# FPGA_0.net
KiCad netlist of a schematic drawn in Altium Designer
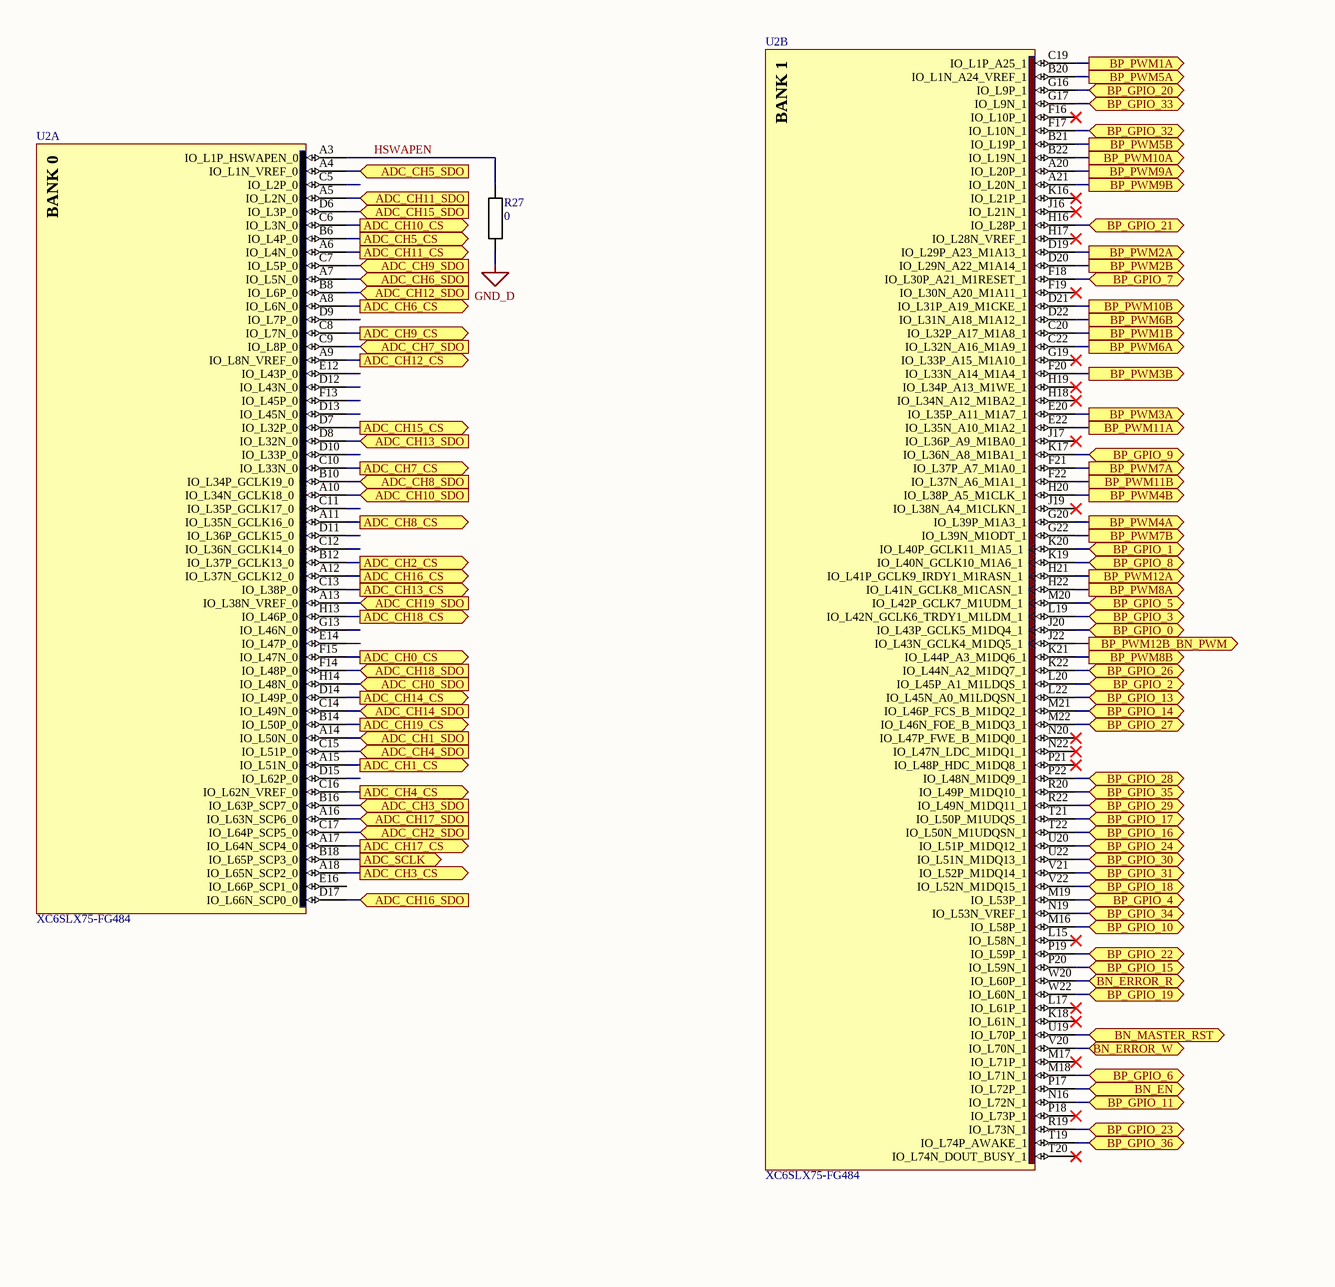
[diagram p0: FPGA_0.SchDoc, left]
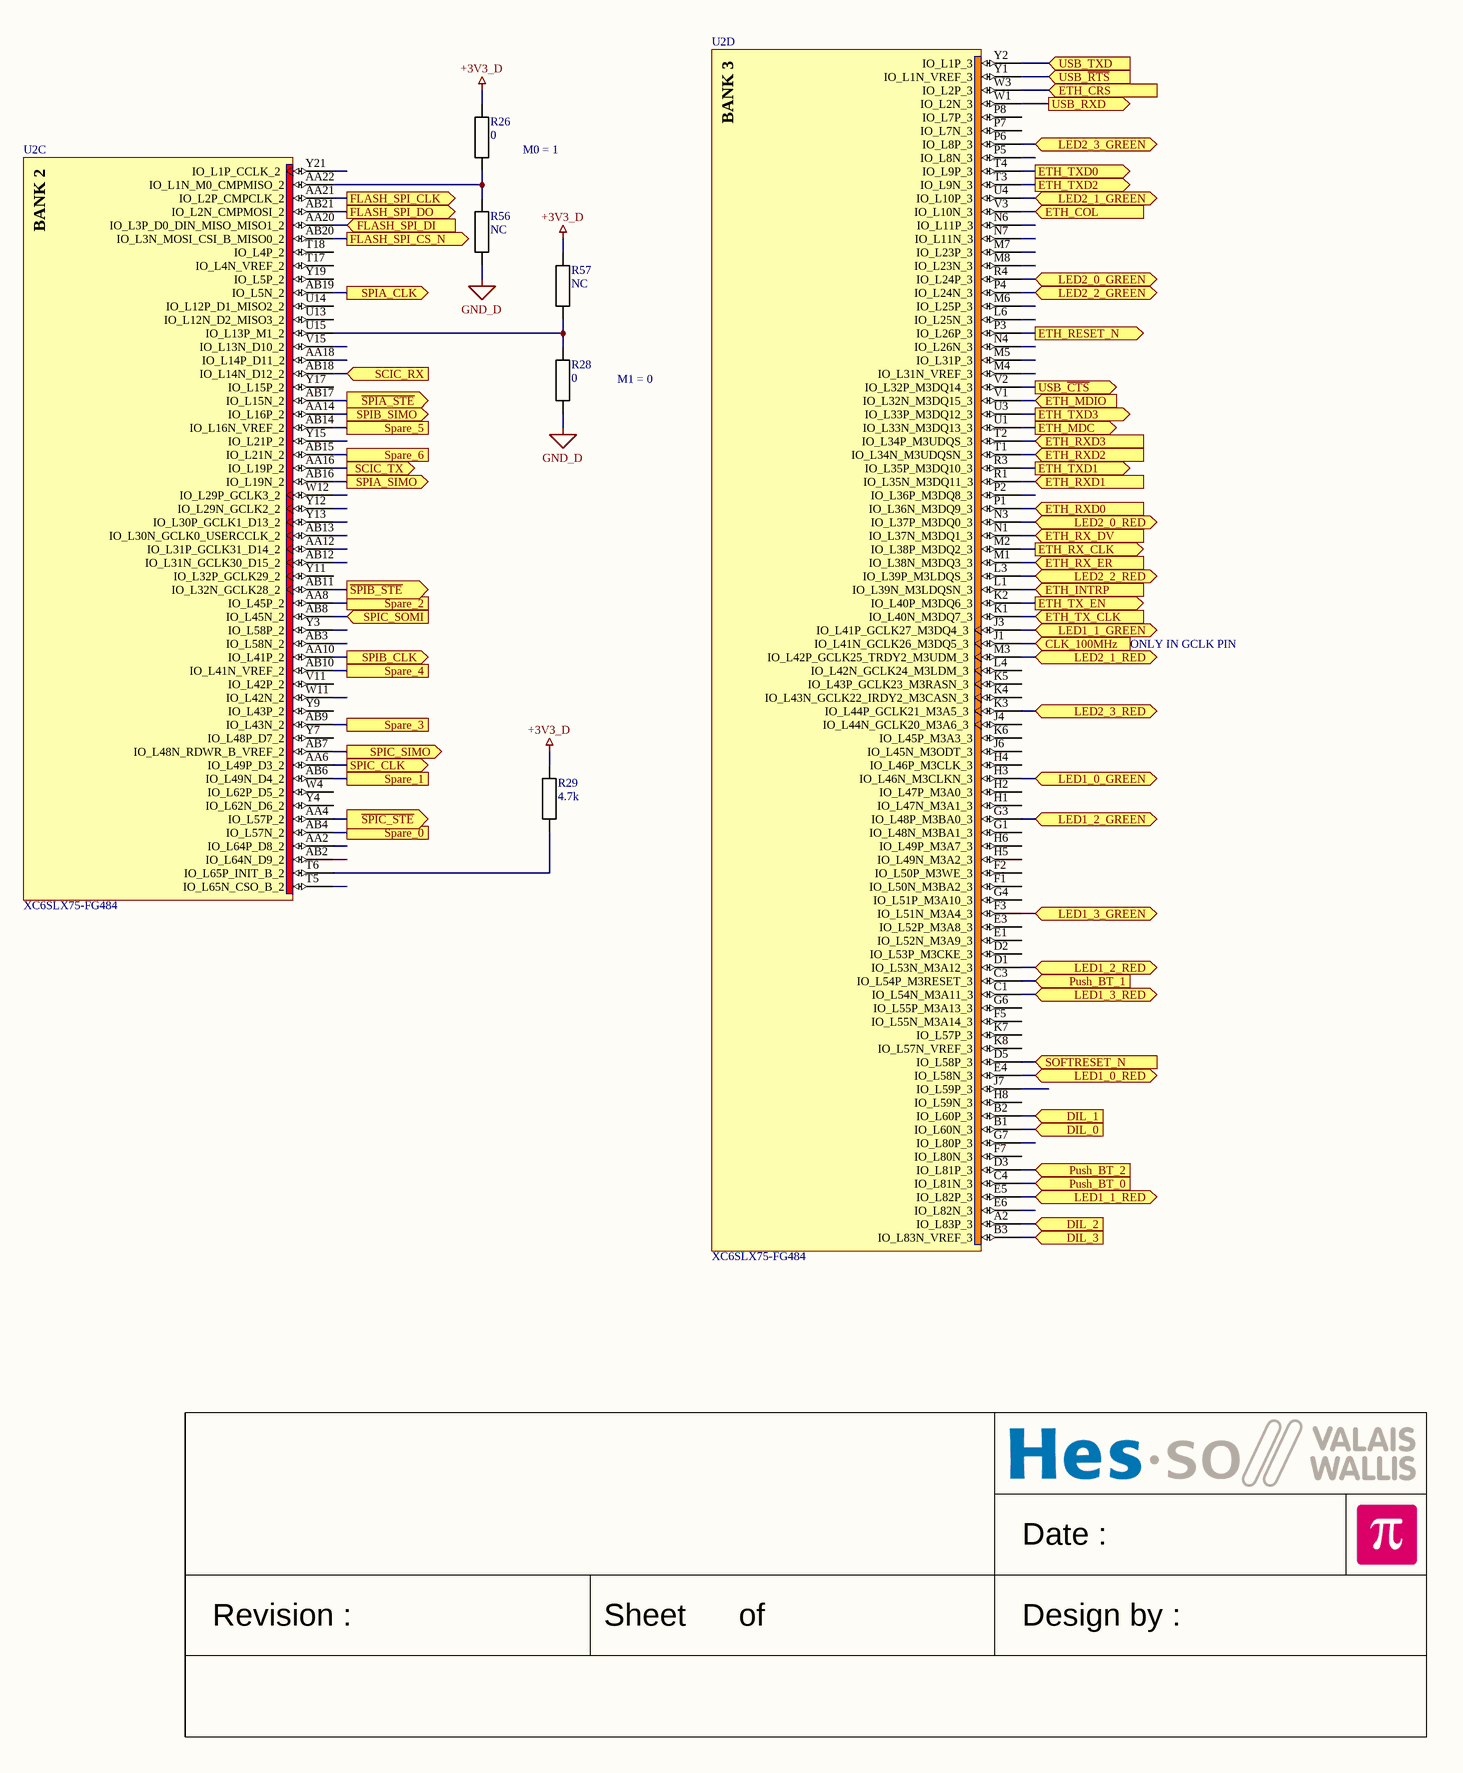
[diagram p1: FPGA_0.SchDoc, right]

(export (version "E")
  (design (tool "Eeschema 10.0.6"))
  (components
    (comp (ref "R26")
      (value "0")
      (footprint "RESISTOR 2012 REFLOW")
      (description "Resistor 1% 50V 125mW 2012(0805)")
      (libsource (lib "Resistor") (part "Resistor"))
    )
    (comp (ref "R27")
      (value "0")
      (footprint "RESISTOR 2012 REFLOW")
      (description "Resistor 1% 50V 125mW 2012(0805)")
      (libsource (lib "Resistor") (part "Resistor"))
    )
    (comp (ref "R28")
      (value "0")
      (footprint "RESISTOR 2012 REFLOW")
      (description "Resistor 1% 50V 125mW 2012(0805)")
      (libsource (lib "Resistor") (part "Resistor"))
    )
    (comp (ref "R29")
      (value "4.7k")
      (footprint "RESISTOR 2012 REFLOW")
      (description "Resistor 1% 50V 125mW 2012(0805)")
      (libsource (lib "Resistor") (part "Resistor"))
    )
    (comp (ref "R56")
      (value "NC")
      (footprint "RESISTOR 2012 REFLOW")
      (description "Resistor 1% 50V 125mW 2012(0805)")
      (libsource (lib "Resistor") (part "Resistor"))
    )
    (comp (ref "R57")
      (value "NC")
      (footprint "RESISTOR 2012 REFLOW")
      (description "Resistor 1% 50V 125mW 2012(0805)")
      (libsource (lib "Resistor") (part "Resistor"))
    )
    (comp (ref "U2")
      (value "XC6SLX75-FG484")
      (footprint "BGA484 P1.0 C23X23 H2.2")
      (description "Spartan-6 LXT 1.2V FPGA, 268 User I/Os, 484-Ball Fine-Pitch BGA (1.0mm Pitch)")
      (libsource (lib "Processor") (part "XC6SLX75-FG484"))
    )
  )
  (nets
    (net (code "1") (name "+3V3_D") (class "Default")
      (node (ref "R26") (pin "2") (pinfunction "2_2") (pintype "passive"))
      (node (ref "R29") (pin "2") (pinfunction "2_2") (pintype "passive"))
      (node (ref "R57") (pin "2") (pinfunction "2_2") (pintype "passive"))
    )
    (net (code "2") (name "/ADC_CH0_CS") (class "Default")
      (node (ref "U2") (pin "F15") (pinfunction "IO_L47N_0_F15") (pintype "bidirectional"))
    )
    (net (code "3") (name "/ADC_CH0_SDO") (class "Default")
      (node (ref "U2") (pin "H14") (pinfunction "IO_L48N_0_H14") (pintype "bidirectional"))
    )
    (net (code "4") (name "/ADC_CH1_CS") (class "Default")
      (node (ref "U2") (pin "A15") (pinfunction "IO_L51N_0_A15") (pintype "bidirectional"))
    )
    (net (code "5") (name "/ADC_CH1_SDO") (class "Default")
      (node (ref "U2") (pin "A14") (pinfunction "IO_L50N_0_A14") (pintype "bidirectional"))
    )
    (net (code "6") (name "/ADC_CH2_CS") (class "Default")
      (node (ref "U2") (pin "B12") (pinfunction "IO_L37P_GCLK13_0_B12") (pintype "bidirectional"))
    )
    (net (code "7") (name "/ADC_CH2_SDO") (class "Default")
      (node (ref "U2") (pin "C17") (pinfunction "IO_L64P_SCP5_0_C17") (pintype "bidirectional"))
    )
    (net (code "8") (name "/ADC_CH3_CS") (class "Default")
      (node (ref "U2") (pin "A18") (pinfunction "IO_L65N_SCP2_0_A18") (pintype "bidirectional"))
    )
    (net (code "9") (name "/ADC_CH3_SDO") (class "Default")
      (node (ref "U2") (pin "B16") (pinfunction "IO_L63P_SCP7_0_B16") (pintype "bidirectional"))
    )
    (net (code "10") (name "/ADC_CH4_CS") (class "Default")
      (node (ref "U2") (pin "C16") (pinfunction "IO_L62N_VREF_0_C16") (pintype "bidirectional"))
    )
    (net (code "11") (name "/ADC_CH4_SDO") (class "Default")
      (node (ref "U2") (pin "C15") (pinfunction "IO_L51P_0_C15") (pintype "bidirectional"))
    )
    (net (code "12") (name "/ADC_CH5_CS") (class "Default")
      (node (ref "U2") (pin "B6") (pinfunction "IO_L4P_0_B6") (pintype "bidirectional"))
    )
    (net (code "13") (name "/ADC_CH5_SDO") (class "Default")
      (node (ref "U2") (pin "A4") (pinfunction "IO_L1N_VREF_0_A4") (pintype "bidirectional"))
    )
    (net (code "14") (name "/ADC_CH6_CS") (class "Default")
      (node (ref "U2") (pin "A8") (pinfunction "IO_L6N_0_A8") (pintype "bidirectional"))
    )
    (net (code "15") (name "/ADC_CH6_SDO") (class "Default")
      (node (ref "U2") (pin "A7") (pinfunction "IO_L5N_0_A7") (pintype "bidirectional"))
    )
    (net (code "16") (name "/ADC_CH7_CS") (class "Default")
      (node (ref "U2") (pin "C10") (pinfunction "IO_L33N_0_C10") (pintype "bidirectional"))
    )
    (net (code "17") (name "/ADC_CH7_SDO") (class "Default")
      (node (ref "U2") (pin "C9") (pinfunction "IO_L8P_0_C9") (pintype "bidirectional"))
    )
    (net (code "18") (name "/ADC_CH8_CS") (class "Default")
      (node (ref "U2") (pin "A11") (pinfunction "IO_L35N_GCLK16_0_A11") (pintype "bidirectional"))
    )
    (net (code "19") (name "/ADC_CH8_SDO") (class "Default")
      (node (ref "U2") (pin "B10") (pinfunction "IO_L34P_GCLK19_0_B10") (pintype "bidirectional"))
    )
    (net (code "20") (name "/ADC_CH9_CS") (class "Default")
      (node (ref "U2") (pin "C8") (pinfunction "IO_L7N_0_C8") (pintype "bidirectional"))
    )
    (net (code "21") (name "/ADC_CH9_SDO") (class "Default")
      (node (ref "U2") (pin "C7") (pinfunction "IO_L5P_0_C7") (pintype "bidirectional"))
    )
    (net (code "22") (name "/ADC_CH10_CS") (class "Default")
      (node (ref "U2") (pin "C6") (pinfunction "IO_L3N_0_C6") (pintype "bidirectional"))
    )
    (net (code "23") (name "/ADC_CH10_SDO") (class "Default")
      (node (ref "U2") (pin "A10") (pinfunction "IO_L34N_GCLK18_0_A10") (pintype "bidirectional"))
    )
    (net (code "24") (name "/ADC_CH11_CS") (class "Default")
      (node (ref "U2") (pin "A6") (pinfunction "IO_L4N_0_A6") (pintype "bidirectional"))
    )
    (net (code "25") (name "/ADC_CH11_SDO") (class "Default")
      (node (ref "U2") (pin "A5") (pinfunction "IO_L2N_0_A5") (pintype "bidirectional"))
    )
    (net (code "26") (name "/ADC_CH12_CS") (class "Default")
      (node (ref "U2") (pin "A9") (pinfunction "IO_L8N_VREF_0_A9") (pintype "bidirectional"))
    )
    (net (code "27") (name "/ADC_CH12_SDO") (class "Default")
      (node (ref "U2") (pin "B8") (pinfunction "IO_L6P_0_B8") (pintype "bidirectional"))
    )
    (net (code "28") (name "/ADC_CH13_CS") (class "Default")
      (node (ref "U2") (pin "C13") (pinfunction "IO_L38P_0_C13") (pintype "bidirectional"))
    )
    (net (code "29") (name "/ADC_CH13_SDO") (class "Default")
      (node (ref "U2") (pin "D8") (pinfunction "IO_L32N_0_D8") (pintype "bidirectional"))
    )
    (net (code "30") (name "/ADC_CH14_CS") (class "Default")
      (node (ref "U2") (pin "D14") (pinfunction "IO_L49P_0_D14") (pintype "bidirectional"))
    )
    (net (code "31") (name "/ADC_CH14_SDO") (class "Default")
      (node (ref "U2") (pin "C14") (pinfunction "IO_L49N_0_C14") (pintype "bidirectional"))
    )
    (net (code "32") (name "/ADC_CH15_CS") (class "Default")
      (node (ref "U2") (pin "D7") (pinfunction "IO_L32P_0_D7") (pintype "bidirectional"))
    )
    (net (code "33") (name "/ADC_CH15_SDO") (class "Default")
      (node (ref "U2") (pin "D6") (pinfunction "IO_L3P_0_D6") (pintype "bidirectional"))
    )
    (net (code "34") (name "/ADC_CH16_CS") (class "Default")
      (node (ref "U2") (pin "A12") (pinfunction "IO_L37N_GCLK12_0_A12") (pintype "bidirectional"))
    )
    (net (code "35") (name "/ADC_CH16_SDO") (class "Default")
      (node (ref "U2") (pin "D17") (pinfunction "IO_L66N_SCP0_0_D17") (pintype "bidirectional"))
    )
    (net (code "36") (name "/ADC_CH17_CS") (class "Default")
      (node (ref "U2") (pin "A17") (pinfunction "IO_L64N_SCP4_0_A17") (pintype "bidirectional"))
    )
    (net (code "37") (name "/ADC_CH17_SDO") (class "Default")
      (node (ref "U2") (pin "A16") (pinfunction "IO_L63N_SCP6_0_A16") (pintype "bidirectional"))
    )
    (net (code "38") (name "/ADC_CH18_CS") (class "Default")
      (node (ref "U2") (pin "H13") (pinfunction "IO_L46P_0_H13") (pintype "bidirectional"))
    )
    (net (code "39") (name "/ADC_CH18_SDO") (class "Default")
      (node (ref "U2") (pin "F14") (pinfunction "IO_L48P_0_F14") (pintype "bidirectional"))
    )
    (net (code "40") (name "/ADC_CH19_CS") (class "Default")
      (node (ref "U2") (pin "B14") (pinfunction "IO_L50P_0_B14") (pintype "bidirectional"))
    )
    (net (code "41") (name "/ADC_CH19_SDO") (class "Default")
      (node (ref "U2") (pin "A13") (pinfunction "IO_L38N_VREF_0_A13") (pintype "bidirectional"))
    )
    (net (code "42") (name "/ADC_SCLK") (class "Default")
      (node (ref "U2") (pin "B18") (pinfunction "IO_L65P_SCP3_0_B18") (pintype "bidirectional"))
    )
    (net (code "43") (name "/BN_EN") (class "Default")
      (node (ref "U2") (pin "P17") (pinfunction "IO_L72P_1_P17") (pintype "bidirectional"))
    )
    (net (code "44") (name "/BN_ERROR_R") (class "Default")
      (node (ref "U2") (pin "W20") (pinfunction "IO_L60P_1_W20") (pintype "bidirectional"))
    )
    (net (code "45") (name "/BN_ERROR_W") (class "Default")
      (node (ref "U2") (pin "V20") (pinfunction "IO_L70N_1_V20") (pintype "bidirectional"))
    )
    (net (code "46") (name "/BN_MASTER_RST") (class "Default")
      (node (ref "U2") (pin "U19") (pinfunction "IO_L70P_1_U19") (pintype "bidirectional"))
    )
    (net (code "47") (name "/BP_GPIO_0") (class "Default")
      (node (ref "U2") (pin "J20") (pinfunction "IO_L43P_GCLK5_M1DQ4_1_J20") (pintype "bidirectional"))
    )
    (net (code "48") (name "/BP_GPIO_1") (class "Default")
      (node (ref "U2") (pin "K20") (pinfunction "IO_L40P_GCLK11_M1A5_1_K20") (pintype "bidirectional"))
    )
    (net (code "49") (name "/BP_GPIO_2") (class "Default")
      (node (ref "U2") (pin "L20") (pinfunction "IO_L45P_A1_M1LDQS_1_L20") (pintype "bidirectional"))
    )
    (net (code "50") (name "/BP_GPIO_3") (class "Default")
      (node (ref "U2") (pin "L19") (pinfunction "IO_L42N_GCLK6_TRDY1_M1LDM_1_L19") (pintype "bidirectional"))
    )
    (net (code "51") (name "/BP_GPIO_4") (class "Default")
      (node (ref "U2") (pin "M19") (pinfunction "IO_L53P_1_M19") (pintype "bidirectional"))
    )
    (net (code "52") (name "/BP_GPIO_5") (class "Default")
      (node (ref "U2") (pin "M20") (pinfunction "IO_L42P_GCLK7_M1UDM_1_M20") (pintype "bidirectional"))
    )
    (net (code "53") (name "/BP_GPIO_6") (class "Default")
      (node (ref "U2") (pin "M18") (pinfunction "IO_L71N_1_M18") (pintype "bidirectional"))
    )
    (net (code "54") (name "/BP_GPIO_7") (class "Default")
      (node (ref "U2") (pin "F18") (pinfunction "IO_L30P_A21_M1RESET_1_F18") (pintype "bidirectional"))
    )
    (net (code "55") (name "/BP_GPIO_8") (class "Default")
      (node (ref "U2") (pin "K19") (pinfunction "IO_L40N_GCLK10_M1A6_1_K19") (pintype "bidirectional"))
    )
    (net (code "56") (name "/BP_GPIO_9") (class "Default")
      (node (ref "U2") (pin "K17") (pinfunction "IO_L36N_A8_M1BA1_1_K17") (pintype "bidirectional"))
    )
    (net (code "57") (name "/BP_GPIO_10") (class "Default")
      (node (ref "U2") (pin "M16") (pinfunction "IO_L58P_1_M16") (pintype "bidirectional"))
    )
    (net (code "58") (name "/BP_GPIO_11") (class "Default")
      (node (ref "U2") (pin "N16") (pinfunction "IO_L72N_1_N16") (pintype "bidirectional"))
    )
    (net (code "59") (name "/BP_GPIO_13") (class "Default")
      (node (ref "U2") (pin "L22") (pinfunction "IO_L45N_A0_M1LDQSN_1_L22") (pintype "bidirectional"))
    )
    (net (code "60") (name "/BP_GPIO_14") (class "Default")
      (node (ref "U2") (pin "M21") (pinfunction "IO_L46P_FCS_B_M1DQ2_1_M21") (pintype "bidirectional"))
    )
    (net (code "61") (name "/BP_GPIO_15") (class "Default")
      (node (ref "U2") (pin "P20") (pinfunction "IO_L59N_1_P20") (pintype "bidirectional"))
    )
    (net (code "62") (name "/BP_GPIO_16") (class "Default")
      (node (ref "U2") (pin "T22") (pinfunction "IO_L50N_M1UDQSN_1_T22") (pintype "bidirectional"))
    )
    (net (code "63") (name "/BP_GPIO_17") (class "Default")
      (node (ref "U2") (pin "T21") (pinfunction "IO_L50P_M1UDQS_1_T21") (pintype "bidirectional"))
    )
    (net (code "64") (name "/BP_GPIO_18") (class "Default")
      (node (ref "U2") (pin "V22") (pinfunction "IO_L52N_M1DQ15_1_V22") (pintype "bidirectional"))
    )
    (net (code "65") (name "/BP_GPIO_19") (class "Default")
      (node (ref "U2") (pin "W22") (pinfunction "IO_L60N_1_W22") (pintype "bidirectional"))
    )
    (net (code "66") (name "/BP_GPIO_20") (class "Default")
      (node (ref "U2") (pin "G16") (pinfunction "IO_L9P_1_G16") (pintype "bidirectional"))
    )
    (net (code "67") (name "/BP_GPIO_21") (class "Default")
      (node (ref "U2") (pin "H16") (pinfunction "IO_L28P_1_H16") (pintype "bidirectional"))
    )
    (net (code "68") (name "/BP_GPIO_22") (class "Default")
      (node (ref "U2") (pin "P19") (pinfunction "IO_L59P_1_P19") (pintype "bidirectional"))
    )
    (net (code "69") (name "/BP_GPIO_23") (class "Default")
      (node (ref "U2") (pin "R19") (pinfunction "IO_L73N_1_R19") (pintype "bidirectional"))
    )
    (net (code "70") (name "/BP_GPIO_24") (class "Default")
      (node (ref "U2") (pin "U20") (pinfunction "IO_L51P_M1DQ12_1_U20") (pintype "bidirectional"))
    )
    (net (code "71") (name "/BP_GPIO_26") (class "Default")
      (node (ref "U2") (pin "K22") (pinfunction "IO_L44N_A2_M1DQ7_1_K22") (pintype "bidirectional"))
    )
    (net (code "72") (name "/BP_GPIO_27") (class "Default")
      (node (ref "U2") (pin "M22") (pinfunction "IO_L46N_FOE_B_M1DQ3_1_M22") (pintype "bidirectional"))
    )
    (net (code "73") (name "/BP_GPIO_28") (class "Default")
      (node (ref "U2") (pin "P22") (pinfunction "IO_L48N_M1DQ9_1_P22") (pintype "bidirectional"))
    )
    (net (code "74") (name "/BP_GPIO_29") (class "Default")
      (node (ref "U2") (pin "R22") (pinfunction "IO_L49N_M1DQ11_1_R22") (pintype "bidirectional"))
    )
    (net (code "75") (name "/BP_GPIO_30") (class "Default")
      (node (ref "U2") (pin "U22") (pinfunction "IO_L51N_M1DQ13_1_U22") (pintype "bidirectional"))
    )
    (net (code "76") (name "/BP_GPIO_31") (class "Default")
      (node (ref "U2") (pin "V21") (pinfunction "IO_L52P_M1DQ14_1_V21") (pintype "bidirectional"))
    )
    (net (code "77") (name "/BP_GPIO_32") (class "Default")
      (node (ref "U2") (pin "F17") (pinfunction "IO_L10N_1_F17") (pintype "bidirectional"))
    )
    (net (code "78") (name "/BP_GPIO_33") (class "Default")
      (node (ref "U2") (pin "G17") (pinfunction "IO_L9N_1_G17") (pintype "bidirectional"))
    )
    (net (code "79") (name "/BP_GPIO_34") (class "Default")
      (node (ref "U2") (pin "N19") (pinfunction "IO_L53N_VREF_1_N19") (pintype "bidirectional"))
    )
    (net (code "80") (name "/BP_GPIO_35") (class "Default")
      (node (ref "U2") (pin "R20") (pinfunction "IO_L49P_M1DQ10_1_R20") (pintype "bidirectional"))
    )
    (net (code "81") (name "/BP_GPIO_36") (class "Default")
      (node (ref "U2") (pin "T19") (pinfunction "IO_L74P_AWAKE_1_T19") (pintype "bidirectional"))
    )
    (net (code "82") (name "/BP_PWM1A") (class "Default")
      (node (ref "U2") (pin "C19") (pinfunction "IO_L1P_A25_1_C19") (pintype "bidirectional"))
    )
    (net (code "83") (name "/BP_PWM1B") (class "Default")
      (node (ref "U2") (pin "C20") (pinfunction "IO_L32P_A17_M1A8_1_C20") (pintype "bidirectional"))
    )
    (net (code "84") (name "/BP_PWM2A") (class "Default")
      (node (ref "U2") (pin "D19") (pinfunction "IO_L29P_A23_M1A13_1_D19") (pintype "bidirectional"))
    )
    (net (code "85") (name "/BP_PWM2B") (class "Default")
      (node (ref "U2") (pin "D20") (pinfunction "IO_L29N_A22_M1A14_1_D20") (pintype "bidirectional"))
    )
    (net (code "86") (name "/BP_PWM3A") (class "Default")
      (node (ref "U2") (pin "E20") (pinfunction "IO_L35P_A11_M1A7_1_E20") (pintype "bidirectional"))
    )
    (net (code "87") (name "/BP_PWM3B") (class "Default")
      (node (ref "U2") (pin "F20") (pinfunction "IO_L33N_A14_M1A4_1_F20") (pintype "bidirectional"))
    )
    (net (code "88") (name "/BP_PWM4A") (class "Default")
      (node (ref "U2") (pin "G20") (pinfunction "IO_L39P_M1A3_1_G20") (pintype "bidirectional"))
    )
    (net (code "89") (name "/BP_PWM4B") (class "Default")
      (node (ref "U2") (pin "H20") (pinfunction "IO_L38P_A5_M1CLK_1_H20") (pintype "bidirectional"))
    )
    (net (code "90") (name "/BP_PWM5A") (class "Default")
      (node (ref "U2") (pin "B20") (pinfunction "IO_L1N_A24_VREF_1_B20") (pintype "bidirectional"))
    )
    (net (code "91") (name "/BP_PWM5B") (class "Default")
      (node (ref "U2") (pin "B21") (pinfunction "IO_L19P_1_B21") (pintype "bidirectional"))
    )
    (net (code "92") (name "/BP_PWM6A") (class "Default")
      (node (ref "U2") (pin "C22") (pinfunction "IO_L32N_A16_M1A9_1_C22") (pintype "bidirectional"))
    )
    (net (code "93") (name "/BP_PWM6B") (class "Default")
      (node (ref "U2") (pin "D22") (pinfunction "IO_L31N_A18_M1A12_1_D22") (pintype "bidirectional"))
    )
    (net (code "94") (name "/BP_PWM7A") (class "Default")
      (node (ref "U2") (pin "F21") (pinfunction "IO_L37P_A7_M1A0_1_F21") (pintype "bidirectional"))
    )
    (net (code "95") (name "/BP_PWM7B") (class "Default")
      (node (ref "U2") (pin "G22") (pinfunction "IO_L39N_M1ODT_1_G22") (pintype "bidirectional"))
    )
    (net (code "96") (name "/BP_PWM8A") (class "Default")
      (node (ref "U2") (pin "H22") (pinfunction "IO_L41N_GCLK8_M1CASN_1_H22") (pintype "bidirectional"))
    )
    (net (code "97") (name "/BP_PWM8B") (class "Default")
      (node (ref "U2") (pin "K21") (pinfunction "IO_L44P_A3_M1DQ6_1_K21") (pintype "bidirectional"))
    )
    (net (code "98") (name "/BP_PWM9A") (class "Default")
      (node (ref "U2") (pin "A20") (pinfunction "IO_L20P_1_A20") (pintype "bidirectional"))
    )
    (net (code "99") (name "/BP_PWM9B") (class "Default")
      (node (ref "U2") (pin "A21") (pinfunction "IO_L20N_1_A21") (pintype "bidirectional"))
    )
    (net (code "100") (name "/BP_PWM10A") (class "Default")
      (node (ref "U2") (pin "B22") (pinfunction "IO_L19N_1_B22") (pintype "bidirectional"))
    )
    (net (code "101") (name "/BP_PWM10B") (class "Default")
      (node (ref "U2") (pin "D21") (pinfunction "IO_L31P_A19_M1CKE_1_D21") (pintype "bidirectional"))
    )
    (net (code "102") (name "/BP_PWM11A") (class "Default")
      (node (ref "U2") (pin "E22") (pinfunction "IO_L35N_A10_M1A2_1_E22") (pintype "bidirectional"))
    )
    (net (code "103") (name "/BP_PWM11B") (class "Default")
      (node (ref "U2") (pin "F22") (pinfunction "IO_L37N_A6_M1A1_1_F22") (pintype "bidirectional"))
    )
    (net (code "104") (name "/BP_PWM12A") (class "Default")
      (node (ref "U2") (pin "H21") (pinfunction "IO_L41P_GCLK9_IRDY1_M1RASN_1_H21") (pintype "bidirectional"))
    )
    (net (code "105") (name "/BP_PWM12B_BN_PWM") (class "Default")
      (node (ref "U2") (pin "J22") (pinfunction "IO_L43N_GCLK4_M1DQ5_1_J22") (pintype "bidirectional"))
    )
    (net (code "106") (name "/CLK_100MHz") (class "Default")
      (node (ref "U2") (pin "J1") (pinfunction "IO_L41N_GCLK26_M3DQ5_3_J1") (pintype "bidirectional"))
    )
    (net (code "107") (name "/DIL_0") (class "Default")
      (node (ref "U2") (pin "B1") (pinfunction "IO_L60N_3_B1") (pintype "bidirectional"))
    )
    (net (code "108") (name "/DIL_1") (class "Default")
      (node (ref "U2") (pin "B2") (pinfunction "IO_L60P_3_B2") (pintype "bidirectional"))
    )
    (net (code "109") (name "/DIL_2") (class "Default")
      (node (ref "U2") (pin "A2") (pinfunction "IO_L83P_3_A2") (pintype "bidirectional"))
    )
    (net (code "110") (name "/DIL_3") (class "Default")
      (node (ref "U2") (pin "B3") (pinfunction "IO_L83N_VREF_3_B3") (pintype "bidirectional"))
    )
    (net (code "111") (name "/ETH_COL") (class "Default")
      (node (ref "U2") (pin "V3") (pinfunction "IO_L10N_3_V3") (pintype "bidirectional"))
    )
    (net (code "112") (name "/ETH_CRS") (class "Default")
      (node (ref "U2") (pin "W3") (pinfunction "IO_L2P_3_W3") (pintype "bidirectional"))
    )
    (net (code "113") (name "/ETH_INTRP") (class "Default")
      (node (ref "U2") (pin "L1") (pinfunction "IO_L39N_M3LDQSN_3_L1") (pintype "bidirectional"))
    )
    (net (code "114") (name "/ETH_MDC") (class "Default")
      (node (ref "U2") (pin "U1") (pinfunction "IO_L33N_M3DQ13_3_U1") (pintype "bidirectional"))
    )
    (net (code "115") (name "/ETH_MDIO") (class "Default")
      (node (ref "U2") (pin "V1") (pinfunction "IO_L32N_M3DQ15_3_V1") (pintype "bidirectional"))
    )
    (net (code "116") (name "/ETH_RESET_N") (class "Default")
      (node (ref "U2") (pin "P3") (pinfunction "IO_L26P_3_P3") (pintype "bidirectional"))
    )
    (net (code "117") (name "/ETH_RXD0") (class "Default")
      (node (ref "U2") (pin "P1") (pinfunction "IO_L36N_M3DQ9_3_P1") (pintype "bidirectional"))
    )
    (net (code "118") (name "/ETH_RXD1") (class "Default")
      (node (ref "U2") (pin "R1") (pinfunction "IO_L35N_M3DQ11_3_R1") (pintype "bidirectional"))
    )
    (net (code "119") (name "/ETH_RXD2") (class "Default")
      (node (ref "U2") (pin "T1") (pinfunction "IO_L34N_M3UDQSN_3_T1") (pintype "bidirectional"))
    )
    (net (code "120") (name "/ETH_RXD3") (class "Default")
      (node (ref "U2") (pin "T2") (pinfunction "IO_L34P_M3UDQS_3_T2") (pintype "bidirectional"))
    )
    (net (code "121") (name "/ETH_RX_CLK") (class "Default")
      (node (ref "U2") (pin "M2") (pinfunction "IO_L38P_M3DQ2_3_M2") (pintype "bidirectional"))
    )
    (net (code "122") (name "/ETH_RX_DV") (class "Default")
      (node (ref "U2") (pin "N1") (pinfunction "IO_L37N_M3DQ1_3_N1") (pintype "bidirectional"))
    )
    (net (code "123") (name "/ETH_RX_ER") (class "Default")
      (node (ref "U2") (pin "M1") (pinfunction "IO_L38N_M3DQ3_3_M1") (pintype "bidirectional"))
    )
    (net (code "124") (name "/ETH_TXD0") (class "Default")
      (node (ref "U2") (pin "T4") (pinfunction "IO_L9P_3_T4") (pintype "bidirectional"))
    )
    (net (code "125") (name "/ETH_TXD1") (class "Default")
      (node (ref "U2") (pin "R3") (pinfunction "IO_L35P_M3DQ10_3_R3") (pintype "bidirectional"))
    )
    (net (code "126") (name "/ETH_TXD2") (class "Default")
      (node (ref "U2") (pin "T3") (pinfunction "IO_L9N_3_T3") (pintype "bidirectional"))
    )
    (net (code "127") (name "/ETH_TXD3") (class "Default")
      (node (ref "U2") (pin "U3") (pinfunction "IO_L33P_M3DQ12_3_U3") (pintype "bidirectional"))
    )
    (net (code "128") (name "/ETH_TX_CLK") (class "Default")
      (node (ref "U2") (pin "K1") (pinfunction "IO_L40N_M3DQ7_3_K1") (pintype "bidirectional"))
    )
    (net (code "129") (name "/ETH_TX_EN") (class "Default")
      (node (ref "U2") (pin "K2") (pinfunction "IO_L40P_M3DQ6_3_K2") (pintype "bidirectional"))
    )
    (net (code "130") (name "/FLASH_SPI_CLK") (class "Default")
      (node (ref "U2") (pin "AA21") (pinfunction "IO_L2P_CMPCLK_2_AA21") (pintype "bidirectional"))
    )
    (net (code "131") (name "/FLASH_SPI_CS_N") (class "Default")
      (node (ref "U2") (pin "AB20") (pinfunction "IO_L3N_MOSI_CSI_B_MISO0_2_AB20") (pintype "bidirectional"))
    )
    (net (code "132") (name "/FLASH_SPI_DI") (class "Default")
      (node (ref "U2") (pin "AA20") (pinfunction "IO_L3P_D0_DIN_MISO_MISO1_2_AA20") (pintype "bidirectional"))
    )
    (net (code "133") (name "/FLASH_SPI_DO") (class "Default")
      (node (ref "U2") (pin "AB21") (pinfunction "IO_L2N_CMPMOSI_2_AB21") (pintype "bidirectional"))
    )
    (net (code "134") (name "/HSWAPEN") (class "Default")
      (node (ref "R27") (pin "2") (pinfunction "2_2") (pintype "passive"))
      (node (ref "U2") (pin "A3") (pinfunction "IO_L1P_HSWAPEN_0_A3") (pintype "bidirectional"))
    )
    (net (code "135") (name "/LED1_0_GREEN") (class "Default")
      (node (ref "U2") (pin "H3") (pinfunction "IO_L46N_M3CLKN_3_H3") (pintype "bidirectional"))
    )
    (net (code "136") (name "/LED1_0_RED") (class "Default")
      (node (ref "U2") (pin "E4") (pinfunction "IO_L58N_3_E4") (pintype "bidirectional"))
    )
    (net (code "137") (name "/LED1_1_GREEN") (class "Default")
      (node (ref "U2") (pin "J3") (pinfunction "IO_L41P_GCLK27_M3DQ4_3_J3") (pintype "bidirectional"))
    )
    (net (code "138") (name "/LED1_1_RED") (class "Default")
      (node (ref "U2") (pin "E5") (pinfunction "IO_L82P_3_E5") (pintype "bidirectional"))
    )
    (net (code "139") (name "/LED1_2_GREEN") (class "Default")
      (node (ref "U2") (pin "G3") (pinfunction "IO_L48P_M3BA0_3_G3") (pintype "bidirectional"))
    )
    (net (code "140") (name "/LED1_2_RED") (class "Default")
      (node (ref "U2") (pin "D1") (pinfunction "IO_L53N_M3A12_3_D1") (pintype "bidirectional"))
    )
    (net (code "141") (name "/LED1_3_GREEN") (class "Default")
      (node (ref "U2") (pin "F3") (pinfunction "IO_L51N_M3A4_3_F3") (pintype "bidirectional"))
    )
    (net (code "142") (name "/LED1_3_RED") (class "Default")
      (node (ref "U2") (pin "C1") (pinfunction "IO_L54N_M3A11_3_C1") (pintype "bidirectional"))
    )
    (net (code "143") (name "/LED2_0_GREEN") (class "Default")
      (node (ref "U2") (pin "R4") (pinfunction "IO_L24P_3_R4") (pintype "bidirectional"))
    )
    (net (code "144") (name "/LED2_0_RED") (class "Default")
      (node (ref "U2") (pin "N3") (pinfunction "IO_L37P_M3DQ0_3_N3") (pintype "bidirectional"))
    )
    (net (code "145") (name "/LED2_1_GREEN") (class "Default")
      (node (ref "U2") (pin "U4") (pinfunction "IO_L10P_3_U4") (pintype "bidirectional"))
    )
    (net (code "146") (name "/LED2_1_RED") (class "Default")
      (node (ref "U2") (pin "M3") (pinfunction "IO_L42P_GCLK25_TRDY2_M3UDM_3_M3") (pintype "bidirectional"))
    )
    (net (code "147") (name "/LED2_2_GREEN") (class "Default")
      (node (ref "U2") (pin "P4") (pinfunction "IO_L24N_3_P4") (pintype "bidirectional"))
    )
    (net (code "148") (name "/LED2_2_RED") (class "Default")
      (node (ref "U2") (pin "L3") (pinfunction "IO_L39P_M3LDQS_3_L3") (pintype "bidirectional"))
    )
    (net (code "149") (name "/LED2_3_GREEN") (class "Default")
      (node (ref "U2") (pin "P6") (pinfunction "IO_L8P_3_P6") (pintype "bidirectional"))
    )
    (net (code "150") (name "/LED2_3_RED") (class "Default")
      (node (ref "U2") (pin "K3") (pinfunction "IO_L44P_GCLK21_M3A5_3_K3") (pintype "bidirectional"))
    )
    (net (code "151") (name "/Push_BT_0") (class "Default")
      (node (ref "U2") (pin "C4") (pinfunction "IO_L81N_3_C4") (pintype "bidirectional"))
    )
    (net (code "152") (name "/Push_BT_1") (class "Default")
      (node (ref "U2") (pin "C3") (pinfunction "IO_L54P_M3RESET_3_C3") (pintype "bidirectional"))
    )
    (net (code "153") (name "/Push_BT_2") (class "Default")
      (node (ref "U2") (pin "D3") (pinfunction "IO_L81P_3_D3") (pintype "bidirectional"))
    )
    (net (code "154") (name "/SCIC_RX") (class "Default")
      (node (ref "U2") (pin "AB18") (pinfunction "IO_L14N_D12_2_AB18") (pintype "bidirectional"))
    )
    (net (code "155") (name "/SCIC_TX") (class "Default")
      (node (ref "U2") (pin "AA16") (pinfunction "IO_L19P_2_AA16") (pintype "bidirectional"))
    )
    (net (code "156") (name "/SOFTRESET_N") (class "Default")
      (node (ref "U2") (pin "D5") (pinfunction "IO_L58P_3_D5") (pintype "bidirectional"))
    )
    (net (code "157") (name "/SPIA_CLK") (class "Default")
      (node (ref "U2") (pin "AB19") (pinfunction "IO_L5N_2_AB19") (pintype "bidirectional"))
    )
    (net (code "158") (name "/SPIA_SIMO") (class "Default")
      (node (ref "U2") (pin "AB16") (pinfunction "IO_L19N_2_AB16") (pintype "bidirectional"))
    )
    (net (code "159") (name "/SPIB_CLK") (class "Default")
      (node (ref "U2") (pin "AA10") (pinfunction "IO_L41P_2_AA10") (pintype "bidirectional"))
    )
    (net (code "160") (name "/SPIB_SIMO") (class "Default")
      (node (ref "U2") (pin "AA14") (pinfunction "IO_L16P_2_AA14") (pintype "bidirectional"))
    )
    (net (code "161") (name "/SPIC_CLK") (class "Default")
      (node (ref "U2") (pin "AA6") (pinfunction "IO_L49P_D3_2_AA6") (pintype "bidirectional"))
    )
    (net (code "162") (name "/SPIC_SIMO") (class "Default")
      (node (ref "U2") (pin "AB7") (pinfunction "IO_L48N_RDWR_B_VREF_2_AB7") (pintype "bidirectional"))
    )
    (net (code "163") (name "/SPIC_SOMI") (class "Default")
      (node (ref "U2") (pin "AB8") (pinfunction "IO_L45N_2_AB8") (pintype "bidirectional"))
    )
    (net (code "164") (name "/Spare_0") (class "Default")
      (node (ref "U2") (pin "AB4") (pinfunction "IO_L57N_2_AB4") (pintype "bidirectional"))
    )
    (net (code "165") (name "/Spare_1") (class "Default")
      (node (ref "U2") (pin "AB6") (pinfunction "IO_L49N_D4_2_AB6") (pintype "bidirectional"))
    )
    (net (code "166") (name "/Spare_2") (class "Default")
      (node (ref "U2") (pin "AA8") (pinfunction "IO_L45P_2_AA8") (pintype "bidirectional"))
    )
    (net (code "167") (name "/Spare_3") (class "Default")
      (node (ref "U2") (pin "AB9") (pinfunction "IO_L43N_2_AB9") (pintype "bidirectional"))
    )
    (net (code "168") (name "/Spare_4") (class "Default")
      (node (ref "U2") (pin "AB10") (pinfunction "IO_L41N_VREF_2_AB10") (pintype "bidirectional"))
    )
    (net (code "169") (name "/Spare_5") (class "Default")
      (node (ref "U2") (pin "AB14") (pinfunction "IO_L16N_VREF_2_AB14") (pintype "bidirectional"))
    )
    (net (code "170") (name "/Spare_6") (class "Default")
      (node (ref "U2") (pin "AB15") (pinfunction "IO_L21N_2_AB15") (pintype "bidirectional"))
    )
    (net (code "171") (name "/USB_RXD") (class "Default")
      (node (ref "U2") (pin "W1") (pinfunction "IO_L2N_3_W1") (pintype "bidirectional"))
    )
    (net (code "172") (name "/USB_TXD") (class "Default")
      (node (ref "U2") (pin "Y2") (pinfunction "IO_L1P_3_Y2") (pintype "bidirectional"))
    )
    (net (code "173") (name "/USB_~{CTS}") (class "Default")
      (node (ref "U2") (pin "V2") (pinfunction "IO_L32P_M3DQ14_3_V2") (pintype "bidirectional"))
    )
    (net (code "174") (name "/USB_~{RTS}") (class "Default")
      (node (ref "U2") (pin "Y1") (pinfunction "IO_L1N_VREF_3_Y1") (pintype "bidirectional"))
    )
    (net (code "175") (name "/~{SPIA_STE}") (class "Default")
      (node (ref "U2") (pin "AB17") (pinfunction "IO_L15N_2_AB17") (pintype "bidirectional"))
    )
    (net (code "176") (name "/~{SPIB_STE}") (class "Default")
      (node (ref "U2") (pin "AB11") (pinfunction "IO_L32N_GCLK28_2_AB11") (pintype "bidirectional"))
    )
    (net (code "177") (name "/~{SPIC_STE}") (class "Default")
      (node (ref "U2") (pin "AA4") (pinfunction "IO_L57P_2_AA4") (pintype "bidirectional"))
    )
    (net (code "178") (name "GND_D") (class "Default")
      (node (ref "R27") (pin "1") (pinfunction "1_1") (pintype "passive"))
      (node (ref "R28") (pin "1") (pinfunction "1_1") (pintype "passive"))
      (node (ref "R56") (pin "1") (pinfunction "1_1") (pintype "passive"))
    )
    (net (code "179") (name "Net-(U2C-IO_L1N_M0_CMPMISO_2)") (class "Default")
      (node (ref "R26") (pin "1") (pinfunction "1_1") (pintype "passive"))
      (node (ref "R56") (pin "2") (pinfunction "2_2") (pintype "passive"))
      (node (ref "U2") (pin "AA22") (pinfunction "IO_L1N_M0_CMPMISO_2_AA22") (pintype "bidirectional"))
    )
    (net (code "180") (name "Net-(U2C-IO_L13P_M1_2)") (class "Default")
      (node (ref "R28") (pin "2") (pinfunction "2_2") (pintype "passive"))
      (node (ref "R57") (pin "1") (pinfunction "1_1") (pintype "passive"))
      (node (ref "U2") (pin "U15") (pinfunction "IO_L13P_M1_2_U15") (pintype "bidirectional"))
    )
    (net (code "181") (name "Net-(U2C-IO_L65P_INIT_B_2)") (class "Default")
      (node (ref "R29") (pin "1") (pinfunction "1_1") (pintype "passive"))
      (node (ref "U2") (pin "T6") (pinfunction "IO_L65P_INIT_B_2_T6") (pintype "bidirectional"))
    )
    (net (code "182") (name "unconnected-(U2A-IO_L2P_0-PadC5)") (class "Default")
      (node (ref "U2") (pin "C5") (pinfunction "IO_L2P_0_C5") (pintype "bidirectional"))
    )
    (net (code "183") (name "unconnected-(U2A-IO_L7P_0-PadD9)") (class "Default")
      (node (ref "U2") (pin "D9") (pinfunction "IO_L7P_0_D9") (pintype "bidirectional"))
    )
    (net (code "184") (name "unconnected-(U2A-IO_L33P_0-PadD10)") (class "Default")
      (node (ref "U2") (pin "D10") (pinfunction "IO_L33P_0_D10") (pintype "bidirectional"))
    )
    (net (code "185") (name "unconnected-(U2A-IO_L35P_GCLK17_0-PadC11)") (class "Default")
      (node (ref "U2") (pin "C11") (pinfunction "IO_L35P_GCLK17_0_C11") (pintype "bidirectional"))
    )
    (net (code "186") (name "unconnected-(U2A-IO_L36N_GCLK14_0-PadC12)") (class "Default")
      (node (ref "U2") (pin "C12") (pinfunction "IO_L36N_GCLK14_0_C12") (pintype "bidirectional"))
    )
    (net (code "187") (name "unconnected-(U2A-IO_L36P_GCLK15_0-PadD11)") (class "Default")
      (node (ref "U2") (pin "D11") (pinfunction "IO_L36P_GCLK15_0_D11") (pintype "bidirectional"))
    )
    (net (code "188") (name "unconnected-(U2A-IO_L43N_0-PadD12)") (class "Default")
      (node (ref "U2") (pin "D12") (pinfunction "IO_L43N_0_D12") (pintype "bidirectional"))
    )
    (net (code "189") (name "unconnected-(U2A-IO_L43P_0-PadE12)") (class "Default")
      (node (ref "U2") (pin "E12") (pinfunction "IO_L43P_0_E12") (pintype "bidirectional"))
    )
    (net (code "190") (name "unconnected-(U2A-IO_L45N_0-PadD13)") (class "Default")
      (node (ref "U2") (pin "D13") (pinfunction "IO_L45N_0_D13") (pintype "bidirectional"))
    )
    (net (code "191") (name "unconnected-(U2A-IO_L45P_0-PadF13)") (class "Default")
      (node (ref "U2") (pin "F13") (pinfunction "IO_L45P_0_F13") (pintype "bidirectional"))
    )
    (net (code "192") (name "unconnected-(U2A-IO_L46N_0-PadG13)") (class "Default")
      (node (ref "U2") (pin "G13") (pinfunction "IO_L46N_0_G13") (pintype "bidirectional"))
    )
    (net (code "193") (name "unconnected-(U2A-IO_L47P_0-PadE14)") (class "Default")
      (node (ref "U2") (pin "E14") (pinfunction "IO_L47P_0_E14") (pintype "bidirectional"))
    )
    (net (code "194") (name "unconnected-(U2A-IO_L62P_0-PadD15)") (class "Default")
      (node (ref "U2") (pin "D15") (pinfunction "IO_L62P_0_D15") (pintype "bidirectional"))
    )
    (net (code "195") (name "unconnected-(U2A-IO_L66P_SCP1_0-PadE16)") (class "Default")
      (node (ref "U2") (pin "E16") (pinfunction "IO_L66P_SCP1_0_E16") (pintype "bidirectional"))
    )
    (net (code "196") (name "unconnected-(U2B-IO_L10P_1-PadF16)") (class "Default")
      (node (ref "U2") (pin "F16") (pinfunction "IO_L10P_1_F16") (pintype "bidirectional+no_connect"))
    )
    (net (code "197") (name "unconnected-(U2B-IO_L21N_1-PadJ16)") (class "Default")
      (node (ref "U2") (pin "J16") (pinfunction "IO_L21N_1_J16") (pintype "bidirectional+no_connect"))
    )
    (net (code "198") (name "unconnected-(U2B-IO_L21P_1-PadK16)") (class "Default")
      (node (ref "U2") (pin "K16") (pinfunction "IO_L21P_1_K16") (pintype "bidirectional+no_connect"))
    )
    (net (code "199") (name "unconnected-(U2B-IO_L28N_VREF_1-PadH17)") (class "Default")
      (node (ref "U2") (pin "H17") (pinfunction "IO_L28N_VREF_1_H17") (pintype "bidirectional+no_connect"))
    )
    (net (code "200") (name "unconnected-(U2B-IO_L30N_A20_M1A11_1-PadF19)") (class "Default")
      (node (ref "U2") (pin "F19") (pinfunction "IO_L30N_A20_M1A11_1_F19") (pintype "bidirectional+no_connect"))
    )
    (net (code "201") (name "unconnected-(U2B-IO_L33P_A15_M1A10_1-PadG19)") (class "Default")
      (node (ref "U2") (pin "G19") (pinfunction "IO_L33P_A15_M1A10_1_G19") (pintype "bidirectional+no_connect"))
    )
    (net (code "202") (name "unconnected-(U2B-IO_L34N_A12_M1BA2_1-PadH18)") (class "Default")
      (node (ref "U2") (pin "H18") (pinfunction "IO_L34N_A12_M1BA2_1_H18") (pintype "bidirectional+no_connect"))
    )
    (net (code "203") (name "unconnected-(U2B-IO_L34P_A13_M1WE_1-PadH19)") (class "Default")
      (node (ref "U2") (pin "H19") (pinfunction "IO_L34P_A13_M1WE_1_H19") (pintype "bidirectional+no_connect"))
    )
    (net (code "204") (name "unconnected-(U2B-IO_L36P_A9_M1BA0_1-PadJ17)") (class "Default")
      (node (ref "U2") (pin "J17") (pinfunction "IO_L36P_A9_M1BA0_1_J17") (pintype "bidirectional+no_connect"))
    )
    (net (code "205") (name "unconnected-(U2B-IO_L38N_A4_M1CLKN_1-PadJ19)") (class "Default")
      (node (ref "U2") (pin "J19") (pinfunction "IO_L38N_A4_M1CLKN_1_J19") (pintype "bidirectional+no_connect"))
    )
    (net (code "206") (name "unconnected-(U2B-IO_L47N_LDC_M1DQ1_1-PadN22)") (class "Default")
      (node (ref "U2") (pin "N22") (pinfunction "IO_L47N_LDC_M1DQ1_1_N22") (pintype "bidirectional+no_connect"))
    )
    (net (code "207") (name "unconnected-(U2B-IO_L47P_FWE_B_M1DQ0_1-PadN20)") (class "Default")
      (node (ref "U2") (pin "N20") (pinfunction "IO_L47P_FWE_B_M1DQ0_1_N20") (pintype "bidirectional+no_connect"))
    )
    (net (code "208") (name "unconnected-(U2B-IO_L48P_HDC_M1DQ8_1-PadP21)") (class "Default")
      (node (ref "U2") (pin "P21") (pinfunction "IO_L48P_HDC_M1DQ8_1_P21") (pintype "bidirectional+no_connect"))
    )
    (net (code "209") (name "unconnected-(U2B-IO_L58N_1-PadL15)") (class "Default")
      (node (ref "U2") (pin "L15") (pinfunction "IO_L58N_1_L15") (pintype "bidirectional+no_connect"))
    )
    (net (code "210") (name "unconnected-(U2B-IO_L61N_1-PadK18)") (class "Default")
      (node (ref "U2") (pin "K18") (pinfunction "IO_L61N_1_K18") (pintype "bidirectional+no_connect"))
    )
    (net (code "211") (name "unconnected-(U2B-IO_L61P_1-PadL17)") (class "Default")
      (node (ref "U2") (pin "L17") (pinfunction "IO_L61P_1_L17") (pintype "bidirectional+no_connect"))
    )
    (net (code "212") (name "unconnected-(U2B-IO_L71P_1-PadM17)") (class "Default")
      (node (ref "U2") (pin "M17") (pinfunction "IO_L71P_1_M17") (pintype "bidirectional+no_connect"))
    )
    (net (code "213") (name "unconnected-(U2B-IO_L73P_1-PadP18)") (class "Default")
      (node (ref "U2") (pin "P18") (pinfunction "IO_L73P_1_P18") (pintype "bidirectional+no_connect"))
    )
    (net (code "214") (name "unconnected-(U2B-IO_L74N_DOUT_BUSY_1-PadT20)") (class "Default")
      (node (ref "U2") (pin "T20") (pinfunction "IO_L74N_DOUT_BUSY_1_T20") (pintype "bidirectional+no_connect"))
    )
    (net (code "215") (name "unconnected-(U2C-IO_L1P_CCLK_2-PadY21)") (class "Default")
      (node (ref "U2") (pin "Y21") (pinfunction "IO_L1P_CCLK_2_Y21") (pintype "bidirectional"))
    )
    (net (code "216") (name "unconnected-(U2C-IO_L4N_VREF_2-PadT17)") (class "Default")
      (node (ref "U2") (pin "T17") (pinfunction "IO_L4N_VREF_2_T17") (pintype "bidirectional"))
    )
    (net (code "217") (name "unconnected-(U2C-IO_L4P_2-PadT18)") (class "Default")
      (node (ref "U2") (pin "T18") (pinfunction "IO_L4P_2_T18") (pintype "bidirectional"))
    )
    (net (code "218") (name "unconnected-(U2C-IO_L5P_2-PadY19)") (class "Default")
      (node (ref "U2") (pin "Y19") (pinfunction "IO_L5P_2_Y19") (pintype "bidirectional"))
    )
    (net (code "219") (name "unconnected-(U2C-IO_L12N_D2_MISO3_2-PadU13)") (class "Default")
      (node (ref "U2") (pin "U13") (pinfunction "IO_L12N_D2_MISO3_2_U13") (pintype "bidirectional"))
    )
    (net (code "220") (name "unconnected-(U2C-IO_L12P_D1_MISO2_2-PadU14)") (class "Default")
      (node (ref "U2") (pin "U14") (pinfunction "IO_L12P_D1_MISO2_2_U14") (pintype "bidirectional"))
    )
    (net (code "221") (name "unconnected-(U2C-IO_L13N_D10_2-PadV15)") (class "Default")
      (node (ref "U2") (pin "V15") (pinfunction "IO_L13N_D10_2_V15") (pintype "bidirectional"))
    )
    (net (code "222") (name "unconnected-(U2C-IO_L14P_D11_2-PadAA18)") (class "Default")
      (node (ref "U2") (pin "AA18") (pinfunction "IO_L14P_D11_2_AA18") (pintype "bidirectional"))
    )
    (net (code "223") (name "unconnected-(U2C-IO_L15P_2-PadY17)") (class "Default")
      (node (ref "U2") (pin "Y17") (pinfunction "IO_L15P_2_Y17") (pintype "bidirectional"))
    )
    (net (code "224") (name "unconnected-(U2C-IO_L21P_2-PadY15)") (class "Default")
      (node (ref "U2") (pin "Y15") (pinfunction "IO_L21P_2_Y15") (pintype "bidirectional"))
    )
    (net (code "225") (name "unconnected-(U2C-IO_L29N_GCLK2_2-PadY12)") (class "Default")
      (node (ref "U2") (pin "Y12") (pinfunction "IO_L29N_GCLK2_2_Y12") (pintype "bidirectional"))
    )
    (net (code "226") (name "unconnected-(U2C-IO_L29P_GCLK3_2-PadW12)") (class "Default")
      (node (ref "U2") (pin "W12") (pinfunction "IO_L29P_GCLK3_2_W12") (pintype "bidirectional"))
    )
    (net (code "227") (name "unconnected-(U2C-IO_L30N_GCLK0_USERCCLK_2-PadAB13)") (class "Default")
      (node (ref "U2") (pin "AB13") (pinfunction "IO_L30N_GCLK0_USERCCLK_2_AB13") (pintype "bidirectional"))
    )
    (net (code "228") (name "unconnected-(U2C-IO_L30P_GCLK1_D13_2-PadY13)") (class "Default")
      (node (ref "U2") (pin "Y13") (pinfunction "IO_L30P_GCLK1_D13_2_Y13") (pintype "bidirectional"))
    )
    (net (code "229") (name "unconnected-(U2C-IO_L31N_GCLK30_D15_2-PadAB12)") (class "Default")
      (node (ref "U2") (pin "AB12") (pinfunction "IO_L31N_GCLK30_D15_2_AB12") (pintype "bidirectional"))
    )
    (net (code "230") (name "unconnected-(U2C-IO_L31P_GCLK31_D14_2-PadAA12)") (class "Default")
      (node (ref "U2") (pin "AA12") (pinfunction "IO_L31P_GCLK31_D14_2_AA12") (pintype "bidirectional"))
    )
    (net (code "231") (name "unconnected-(U2C-IO_L32P_GCLK29_2-PadY11)") (class "Default")
      (node (ref "U2") (pin "Y11") (pinfunction "IO_L32P_GCLK29_2_Y11") (pintype "bidirectional"))
    )
    (net (code "232") (name "unconnected-(U2C-IO_L42N_2-PadW11)") (class "Default")
      (node (ref "U2") (pin "W11") (pinfunction "IO_L42N_2_W11") (pintype "bidirectional"))
    )
    (net (code "233") (name "unconnected-(U2C-IO_L42P_2-PadV11)") (class "Default")
      (node (ref "U2") (pin "V11") (pinfunction "IO_L42P_2_V11") (pintype "bidirectional"))
    )
    (net (code "234") (name "unconnected-(U2C-IO_L43P_2-PadY9)") (class "Default")
      (node (ref "U2") (pin "Y9") (pinfunction "IO_L43P_2_Y9") (pintype "bidirectional"))
    )
    (net (code "235") (name "unconnected-(U2C-IO_L48P_D7_2-PadY7)") (class "Default")
      (node (ref "U2") (pin "Y7") (pinfunction "IO_L48P_D7_2_Y7") (pintype "bidirectional"))
    )
    (net (code "236") (name "unconnected-(U2C-IO_L58N_2-PadAB3)") (class "Default")
      (node (ref "U2") (pin "AB3") (pinfunction "IO_L58N_2_AB3") (pintype "bidirectional"))
    )
    (net (code "237") (name "unconnected-(U2C-IO_L58P_2-PadY3)") (class "Default")
      (node (ref "U2") (pin "Y3") (pinfunction "IO_L58P_2_Y3") (pintype "bidirectional"))
    )
    (net (code "238") (name "unconnected-(U2C-IO_L62N_D6_2-PadY4)") (class "Default")
      (node (ref "U2") (pin "Y4") (pinfunction "IO_L62N_D6_2_Y4") (pintype "bidirectional"))
    )
    (net (code "239") (name "unconnected-(U2C-IO_L62P_D5_2-PadW4)") (class "Default")
      (node (ref "U2") (pin "W4") (pinfunction "IO_L62P_D5_2_W4") (pintype "bidirectional"))
    )
    (net (code "240") (name "unconnected-(U2C-IO_L64N_D9_2-PadAB2)") (class "Default")
      (node (ref "U2") (pin "AB2") (pinfunction "IO_L64N_D9_2_AB2") (pintype "bidirectional"))
    )
    (net (code "241") (name "unconnected-(U2C-IO_L64P_D8_2-PadAA2)") (class "Default")
      (node (ref "U2") (pin "AA2") (pinfunction "IO_L64P_D8_2_AA2") (pintype "bidirectional"))
    )
    (net (code "242") (name "unconnected-(U2C-IO_L65N_CSO_B_2-PadT5)") (class "Default")
      (node (ref "U2") (pin "T5") (pinfunction "IO_L65N_CSO_B_2_T5") (pintype "bidirectional"))
    )
    (net (code "243") (name "unconnected-(U2D-IO_L7N_3-PadP7)") (class "Default")
      (node (ref "U2") (pin "P7") (pinfunction "IO_L7N_3_P7") (pintype "bidirectional"))
    )
    (net (code "244") (name "unconnected-(U2D-IO_L7P_3-PadP8)") (class "Default")
      (node (ref "U2") (pin "P8") (pinfunction "IO_L7P_3_P8") (pintype "bidirectional"))
    )
    (net (code "245") (name "unconnected-(U2D-IO_L8N_3-PadP5)") (class "Default")
      (node (ref "U2") (pin "P5") (pinfunction "IO_L8N_3_P5") (pintype "bidirectional"))
    )
    (net (code "246") (name "unconnected-(U2D-IO_L11N_3-PadN7)") (class "Default")
      (node (ref "U2") (pin "N7") (pinfunction "IO_L11N_3_N7") (pintype "bidirectional"))
    )
    (net (code "247") (name "unconnected-(U2D-IO_L11P_3-PadN6)") (class "Default")
      (node (ref "U2") (pin "N6") (pinfunction "IO_L11P_3_N6") (pintype "bidirectional"))
    )
    (net (code "248") (name "unconnected-(U2D-IO_L23N_3-PadM8)") (class "Default")
      (node (ref "U2") (pin "M8") (pinfunction "IO_L23N_3_M8") (pintype "bidirectional"))
    )
    (net (code "249") (name "unconnected-(U2D-IO_L23P_3-PadM7)") (class "Default")
      (node (ref "U2") (pin "M7") (pinfunction "IO_L23P_3_M7") (pintype "bidirectional"))
    )
    (net (code "250") (name "unconnected-(U2D-IO_L25N_3-PadL6)") (class "Default")
      (node (ref "U2") (pin "L6") (pinfunction "IO_L25N_3_L6") (pintype "bidirectional"))
    )
    (net (code "251") (name "unconnected-(U2D-IO_L25P_3-PadM6)") (class "Default")
      (node (ref "U2") (pin "M6") (pinfunction "IO_L25P_3_M6") (pintype "bidirectional"))
    )
    (net (code "252") (name "unconnected-(U2D-IO_L26N_3-PadN4)") (class "Default")
      (node (ref "U2") (pin "N4") (pinfunction "IO_L26N_3_N4") (pintype "bidirectional"))
    )
    (net (code "253") (name "unconnected-(U2D-IO_L31N_VREF_3-PadM4)") (class "Default")
      (node (ref "U2") (pin "M4") (pinfunction "IO_L31N_VREF_3_M4") (pintype "bidirectional"))
    )
    (net (code "254") (name "unconnected-(U2D-IO_L31P_3-PadM5)") (class "Default")
      (node (ref "U2") (pin "M5") (pinfunction "IO_L31P_3_M5") (pintype "bidirectional"))
    )
    (net (code "255") (name "unconnected-(U2D-IO_L36P_M3DQ8_3-PadP2)") (class "Default")
      (node (ref "U2") (pin "P2") (pinfunction "IO_L36P_M3DQ8_3_P2") (pintype "bidirectional"))
    )
    (net (code "256") (name "unconnected-(U2D-IO_L42N_GCLK24_M3LDM_3-PadL4)") (class "Default")
      (node (ref "U2") (pin "L4") (pinfunction "IO_L42N_GCLK24_M3LDM_3_L4") (pintype "bidirectional"))
    )
    (net (code "257") (name "unconnected-(U2D-IO_L43N_GCLK22_IRDY2_M3CASN_3-PadK4)") (class "Default")
      (node (ref "U2") (pin "K4") (pinfunction "IO_L43N_GCLK22_IRDY2_M3CASN_3_K4") (pintype "bidirectional"))
    )
    (net (code "258") (name "unconnected-(U2D-IO_L43P_GCLK23_M3RASN_3-PadK5)") (class "Default")
      (node (ref "U2") (pin "K5") (pinfunction "IO_L43P_GCLK23_M3RASN_3_K5") (pintype "bidirectional"))
    )
    (net (code "259") (name "unconnected-(U2D-IO_L44N_GCLK20_M3A6_3-PadJ4)") (class "Default")
      (node (ref "U2") (pin "J4") (pinfunction "IO_L44N_GCLK20_M3A6_3_J4") (pintype "bidirectional"))
    )
    (net (code "260") (name "unconnected-(U2D-IO_L45N_M3ODT_3-PadJ6)") (class "Default")
      (node (ref "U2") (pin "J6") (pinfunction "IO_L45N_M3ODT_3_J6") (pintype "bidirectional"))
    )
    (net (code "261") (name "unconnected-(U2D-IO_L45P_M3A3_3-PadK6)") (class "Default")
      (node (ref "U2") (pin "K6") (pinfunction "IO_L45P_M3A3_3_K6") (pintype "bidirectional"))
    )
    (net (code "262") (name "unconnected-(U2D-IO_L46P_M3CLK_3-PadH4)") (class "Default")
      (node (ref "U2") (pin "H4") (pinfunction "IO_L46P_M3CLK_3_H4") (pintype "bidirectional"))
    )
    (net (code "263") (name "unconnected-(U2D-IO_L47N_M3A1_3-PadH1)") (class "Default")
      (node (ref "U2") (pin "H1") (pinfunction "IO_L47N_M3A1_3_H1") (pintype "bidirectional"))
    )
    (net (code "264") (name "unconnected-(U2D-IO_L47P_M3A0_3-PadH2)") (class "Default")
      (node (ref "U2") (pin "H2") (pinfunction "IO_L47P_M3A0_3_H2") (pintype "bidirectional"))
    )
    (net (code "265") (name "unconnected-(U2D-IO_L48N_M3BA1_3-PadG1)") (class "Default")
      (node (ref "U2") (pin "G1") (pinfunction "IO_L48N_M3BA1_3_G1") (pintype "bidirectional"))
    )
    (net (code "266") (name "unconnected-(U2D-IO_L49N_M3A2_3-PadH5)") (class "Default")
      (node (ref "U2") (pin "H5") (pinfunction "IO_L49N_M3A2_3_H5") (pintype "bidirectional"))
    )
    (net (code "267") (name "unconnected-(U2D-IO_L49P_M3A7_3-PadH6)") (class "Default")
      (node (ref "U2") (pin "H6") (pinfunction "IO_L49P_M3A7_3_H6") (pintype "bidirectional"))
    )
    (net (code "268") (name "unconnected-(U2D-IO_L50N_M3BA2_3-PadF1)") (class "Default")
      (node (ref "U2") (pin "F1") (pinfunction "IO_L50N_M3BA2_3_F1") (pintype "bidirectional"))
    )
    (net (code "269") (name "unconnected-(U2D-IO_L50P_M3WE_3-PadF2)") (class "Default")
      (node (ref "U2") (pin "F2") (pinfunction "IO_L50P_M3WE_3_F2") (pintype "bidirectional"))
    )
    (net (code "270") (name "unconnected-(U2D-IO_L51P_M3A10_3-PadG4)") (class "Default")
      (node (ref "U2") (pin "G4") (pinfunction "IO_L51P_M3A10_3_G4") (pintype "bidirectional"))
    )
    (net (code "271") (name "unconnected-(U2D-IO_L52N_M3A9_3-PadE1)") (class "Default")
      (node (ref "U2") (pin "E1") (pinfunction "IO_L52N_M3A9_3_E1") (pintype "bidirectional"))
    )
    (net (code "272") (name "unconnected-(U2D-IO_L52P_M3A8_3-PadE3)") (class "Default")
      (node (ref "U2") (pin "E3") (pinfunction "IO_L52P_M3A8_3_E3") (pintype "bidirectional"))
    )
    (net (code "273") (name "unconnected-(U2D-IO_L53P_M3CKE_3-PadD2)") (class "Default")
      (node (ref "U2") (pin "D2") (pinfunction "IO_L53P_M3CKE_3_D2") (pintype "bidirectional"))
    )
    (net (code "274") (name "unconnected-(U2D-IO_L55N_M3A14_3-PadF5)") (class "Default")
      (node (ref "U2") (pin "F5") (pinfunction "IO_L55N_M3A14_3_F5") (pintype "bidirectional"))
    )
    (net (code "275") (name "unconnected-(U2D-IO_L55P_M3A13_3-PadG6)") (class "Default")
      (node (ref "U2") (pin "G6") (pinfunction "IO_L55P_M3A13_3_G6") (pintype "bidirectional"))
    )
    (net (code "276") (name "unconnected-(U2D-IO_L57N_VREF_3-PadK8)") (class "Default")
      (node (ref "U2") (pin "K8") (pinfunction "IO_L57N_VREF_3_K8") (pintype "bidirectional"))
    )
    (net (code "277") (name "unconnected-(U2D-IO_L57P_3-PadK7)") (class "Default")
      (node (ref "U2") (pin "K7") (pinfunction "IO_L57P_3_K7") (pintype "bidirectional"))
    )
    (net (code "278") (name "unconnected-(U2D-IO_L59N_3-PadH8)") (class "Default")
      (node (ref "U2") (pin "H8") (pinfunction "IO_L59N_3_H8") (pintype "bidirectional"))
    )
    (net (code "279") (name "unconnected-(U2D-IO_L59P_3-PadJ7)") (class "Default")
      (node (ref "U2") (pin "J7") (pinfunction "IO_L59P_3_J7") (pintype "bidirectional"))
    )
    (net (code "280") (name "unconnected-(U2D-IO_L80N_3-PadF7)") (class "Default")
      (node (ref "U2") (pin "F7") (pinfunction "IO_L80N_3_F7") (pintype "bidirectional"))
    )
    (net (code "281") (name "unconnected-(U2D-IO_L80P_3-PadG7)") (class "Default")
      (node (ref "U2") (pin "G7") (pinfunction "IO_L80P_3_G7") (pintype "bidirectional"))
    )
    (net (code "282") (name "unconnected-(U2D-IO_L82N_3-PadE6)") (class "Default")
      (node (ref "U2") (pin "E6") (pinfunction "IO_L82N_3_E6") (pintype "bidirectional"))
    )
  )
)
